# angle_led.net
KiCad netlist of a schematic drawn in EAGLE
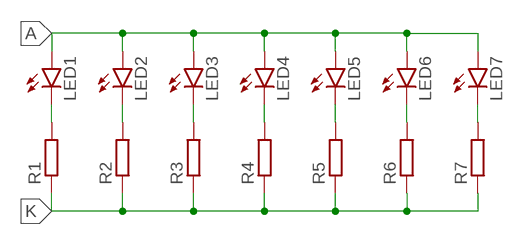
[diagram p0: schematic, sheet 1]

(export (version "E")
  (design (tool "Eeschema 10.0.6"))
  (components
    (comp (ref "LED1")
      (value "LED5MM")
      (footprint "eagle-import:LED5MM")
      (libsource (lib "eagle-import") (part "LED5MM"))
    )
    (comp (ref "LED2")
      (value "LED5MM")
      (footprint "eagle-import:LED5MM")
      (libsource (lib "eagle-import") (part "LED5MM"))
    )
    (comp (ref "LED3")
      (value "LED5MM")
      (footprint "eagle-import:LED5MM")
      (libsource (lib "eagle-import") (part "LED5MM"))
    )
    (comp (ref "LED4")
      (value "LED5MM")
      (footprint "eagle-import:LED5MM")
      (libsource (lib "eagle-import") (part "LED5MM"))
    )
    (comp (ref "LED5")
      (value "LED5MM")
      (footprint "eagle-import:LED5MM")
      (libsource (lib "eagle-import") (part "LED5MM"))
    )
    (comp (ref "LED6")
      (value "LED5MM")
      (footprint "eagle-import:LED5MM")
      (libsource (lib "eagle-import") (part "LED5MM"))
    )
    (comp (ref "LED7")
      (value "LED5MM")
      (footprint "eagle-import:LED5MM")
      (libsource (lib "eagle-import") (part "LED5MM"))
    )
    (comp (ref "R1")
      (value "R-EU_R0603")
      (footprint "eagle-import:R0603")
      (libsource (lib "eagle-import") (part "R-EU_R0603"))
    )
    (comp (ref "R2")
      (value "R-EU_R0603")
      (footprint "eagle-import:R0603")
      (libsource (lib "eagle-import") (part "R-EU_R0603"))
    )
    (comp (ref "R3")
      (value "R-EU_R0603")
      (footprint "eagle-import:R0603")
      (libsource (lib "eagle-import") (part "R-EU_R0603"))
    )
    (comp (ref "R4")
      (value "R-EU_R0603")
      (footprint "eagle-import:R0603")
      (libsource (lib "eagle-import") (part "R-EU_R0603"))
    )
    (comp (ref "R5")
      (value "R-EU_R0603")
      (footprint "eagle-import:R0603")
      (libsource (lib "eagle-import") (part "R-EU_R0603"))
    )
    (comp (ref "R6")
      (value "R-EU_R0603")
      (footprint "eagle-import:R0603")
      (libsource (lib "eagle-import") (part "R-EU_R0603"))
    )
    (comp (ref "R7")
      (value "R-EU_R0603")
      (footprint "eagle-import:R0603")
      (libsource (lib "eagle-import") (part "R-EU_R0603"))
    )
  )
  (nets
    (net (code "1") (name "A") (class "Default")
      (node (ref "LED1") (pin "A") (pinfunction "A_A") (pintype "passive"))
      (node (ref "LED2") (pin "A") (pinfunction "A_A") (pintype "passive"))
      (node (ref "LED3") (pin "A") (pinfunction "A_A") (pintype "passive"))
      (node (ref "LED4") (pin "A") (pinfunction "A_A") (pintype "passive"))
      (node (ref "LED5") (pin "A") (pinfunction "A_A") (pintype "passive"))
      (node (ref "LED6") (pin "A") (pinfunction "A_A") (pintype "passive"))
      (node (ref "LED7") (pin "A") (pinfunction "A_A") (pintype "passive"))
    )
    (net (code "2") (name "K") (class "Default")
      (node (ref "R1") (pin "1") (pinfunction "1_1") (pintype "passive"))
      (node (ref "R2") (pin "1") (pinfunction "1_1") (pintype "passive"))
      (node (ref "R3") (pin "1") (pinfunction "1_1") (pintype "passive"))
      (node (ref "R4") (pin "1") (pinfunction "1_1") (pintype "passive"))
      (node (ref "R5") (pin "1") (pinfunction "1_1") (pintype "passive"))
      (node (ref "R6") (pin "1") (pinfunction "1_1") (pintype "passive"))
      (node (ref "R7") (pin "1") (pinfunction "1_1") (pintype "passive"))
    )
    (net (code "3") (name "Net-(LED1-C)") (class "Default")
      (node (ref "LED1") (pin "K") (pinfunction "C_K") (pintype "passive"))
      (node (ref "R1") (pin "2") (pinfunction "2_2") (pintype "passive"))
    )
    (net (code "4") (name "Net-(LED2-C)") (class "Default")
      (node (ref "LED2") (pin "K") (pinfunction "C_K") (pintype "passive"))
      (node (ref "R2") (pin "2") (pinfunction "2_2") (pintype "passive"))
    )
    (net (code "5") (name "Net-(LED3-C)") (class "Default")
      (node (ref "LED3") (pin "K") (pinfunction "C_K") (pintype "passive"))
      (node (ref "R3") (pin "2") (pinfunction "2_2") (pintype "passive"))
    )
    (net (code "6") (name "Net-(LED4-C)") (class "Default")
      (node (ref "LED4") (pin "K") (pinfunction "C_K") (pintype "passive"))
      (node (ref "R4") (pin "2") (pinfunction "2_2") (pintype "passive"))
    )
    (net (code "7") (name "Net-(LED5-C)") (class "Default")
      (node (ref "LED5") (pin "K") (pinfunction "C_K") (pintype "passive"))
      (node (ref "R5") (pin "2") (pinfunction "2_2") (pintype "passive"))
    )
    (net (code "8") (name "Net-(LED6-C)") (class "Default")
      (node (ref "LED6") (pin "K") (pinfunction "C_K") (pintype "passive"))
      (node (ref "R6") (pin "2") (pinfunction "2_2") (pintype "passive"))
    )
    (net (code "9") (name "Net-(LED7-C)") (class "Default")
      (node (ref "LED7") (pin "K") (pinfunction "C_K") (pintype "passive"))
      (node (ref "R7") (pin "2") (pinfunction "2_2") (pintype "passive"))
    )
  )
)
